# rapidshark-main-breakout-top-mk-1_5.net
KiCad netlist of a schematic drawn in EAGLE
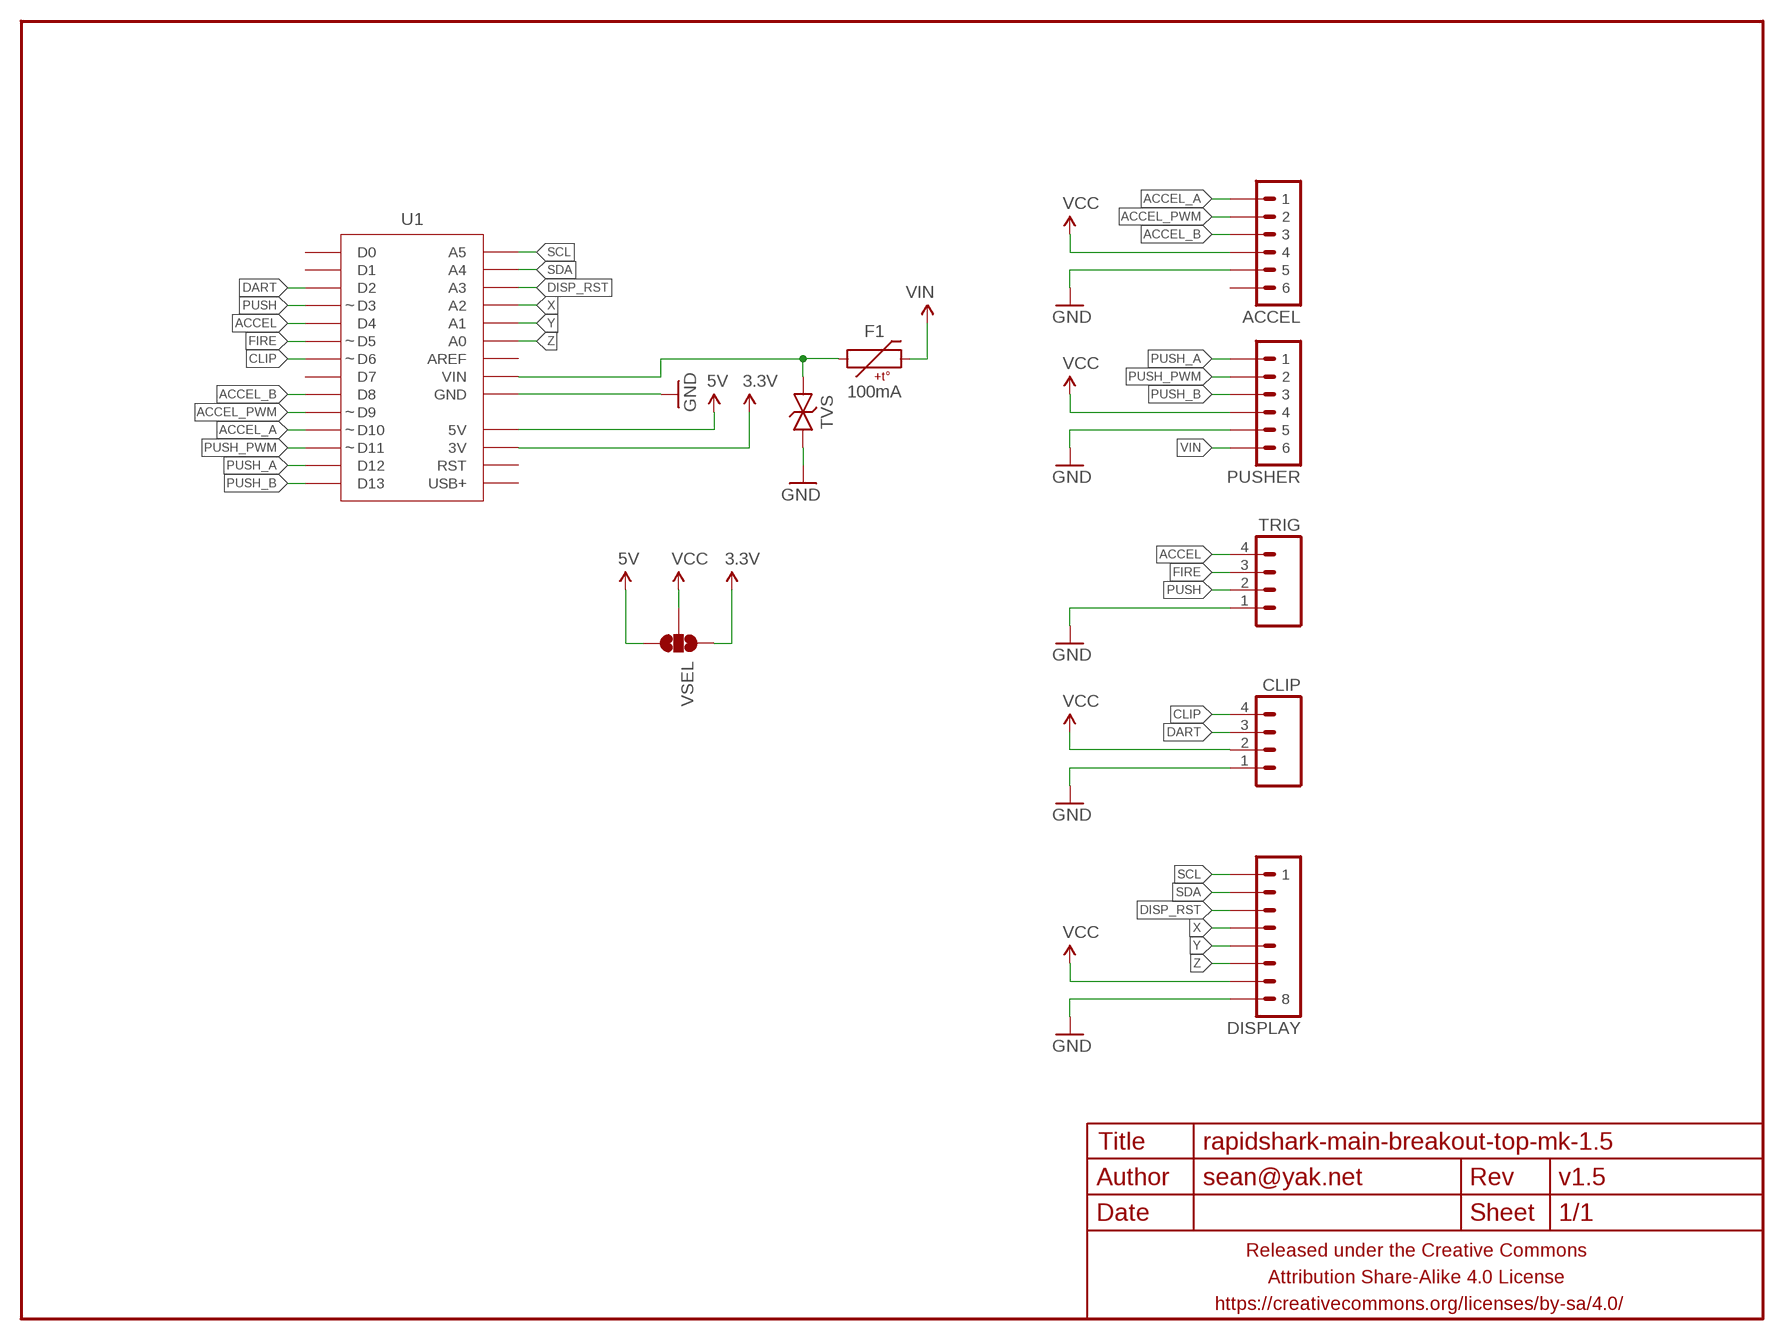
[diagram p0: schematic, sheet 1]

(export (version "E")
  (design (tool "Eeschema 10.0.6"))
  (components
    (comp (ref "ACCEL")
      (value "M06JST-PH-PTH-VERT")
      (footprint "eagle-import:JST-6-PH-VERT-PTH")
      (libsource (lib "eagle-import") (part "M06JST-PH-PTH-VERT"))
    )
    (comp (ref "CLIP")
      (value "M04JST-PTH-VERT")
      (footprint "eagle-import:JST-4-PH-VERT-PTH")
      (libsource (lib "eagle-import") (part "M04JST-PTH-VERT"))
    )
    (comp (ref "DISPLAY")
      (value "M08JST-PH-VERT-PTH")
      (footprint "eagle-import:JST-8-VERT-PTH")
      (libsource (lib "eagle-import") (part "M08JST-PH-VERT-PTH"))
    )
    (comp (ref "F1")
      (value "100mA")
      (footprint "eagle-import:PTC-1206")
      (libsource (lib "eagle-import") (part "PTCSMD"))
    )
    (comp (ref "FRAME1")
      (value "FRAME-LETTERNO_PACKAGE")
      (footprint "eagle-import:DUMMY")
      (fields (field (name "DESIGNER") "sean@yak.net") (field (name "VERSION") "v1.5"))
      (libsource (lib "eagle-import") (part "FRAME-LETTERNO_PACKAGE"))
    )
    (comp (ref "PUSHER")
      (value "M06JST-PH-PTH-VERT")
      (footprint "eagle-import:JST-6-PH-VERT-PTH")
      (libsource (lib "eagle-import") (part "M06JST-PH-PTH-VERT"))
    )
    (comp (ref "TRIG")
      (value "M04JST-PTH-VERT")
      (footprint "eagle-import:JST-4-PH-VERT-PTH")
      (libsource (lib "eagle-import") (part "M04JST-PTH-VERT"))
    )
    (comp (ref "TVS")
      (value "TVSSMA")
      (footprint "eagle-import:SMA-DIODE-TVS-BIDIR")
      (libsource (lib "eagle-import") (part "TVSSMA"))
    )
    (comp (ref "U1")
      (value "ADAFRUIT_METRO_MININOSILK-AMBI2")
      (footprint "eagle-import:ADAFRUIT_METRO_MINI_BACK")
      (libsource (lib "eagle-import") (part "ADAFRUIT_METRO_MININOSILK-AMBI2"))
    )
    (comp (ref "VSEL")
      (value "JUMPER-PAD-3-NOFULL_BOX_SILK")
      (footprint "eagle-import:PAD-JUMPER-3-NO_YES_SILK_FULL_BOX")
      (libsource (lib "eagle-import") (part "JUMPER-PAD-3-NOFULL_BOX_SILK"))
    )
  )
  (nets
    (net (code "1") (name "3.3V") (class "Default")
      (node (ref "U1") (pin "17") (pinfunction "3V_17") (pintype "bidirectional"))
      (node (ref "VSEL") (pin "1") (pinfunction "1_1") (pintype "passive"))
    )
    (net (code "2") (name "5V") (class "Default")
      (node (ref "U1") (pin "18") (pinfunction "5V_18") (pintype "bidirectional"))
      (node (ref "VSEL") (pin "3") (pinfunction "3_3") (pintype "passive"))
    )
    (net (code "3") (name "ACCEL") (class "Default")
      (node (ref "TRIG") (pin "4") (pinfunction "4_4") (pintype "passive"))
      (node (ref "U1") (pin "5") (pinfunction "D4_5") (pintype "bidirectional"))
    )
    (net (code "4") (name "ACCEL_A") (class "Default")
      (node (ref "ACCEL") (pin "1") (pinfunction "1_1") (pintype "passive"))
      (node (ref "U1") (pin "11") (pinfunction "D10_11") (pintype "bidirectional"))
    )
    (net (code "5") (name "ACCEL_B") (class "Default")
      (node (ref "ACCEL") (pin "3") (pinfunction "3_3") (pintype "passive"))
      (node (ref "U1") (pin "9") (pinfunction "D8_9") (pintype "bidirectional"))
    )
    (net (code "6") (name "ACCEL_PWM") (class "Default")
      (node (ref "ACCEL") (pin "2") (pinfunction "2_2") (pintype "passive"))
      (node (ref "U1") (pin "10") (pinfunction "D9_10") (pintype "bidirectional"))
    )
    (net (code "7") (name "CLIP") (class "Default")
      (node (ref "CLIP") (pin "4") (pinfunction "4_4") (pintype "passive"))
      (node (ref "U1") (pin "7") (pinfunction "D6_7") (pintype "bidirectional"))
    )
    (net (code "8") (name "DART") (class "Default")
      (node (ref "CLIP") (pin "3") (pinfunction "3_3") (pintype "passive"))
      (node (ref "U1") (pin "3") (pinfunction "D2_3") (pintype "bidirectional"))
    )
    (net (code "9") (name "DISP_RST") (class "Default")
      (node (ref "DISPLAY") (pin "3") (pinfunction "3_3") (pintype "passive"))
      (node (ref "U1") (pin "26") (pinfunction "A3_26") (pintype "bidirectional"))
    )
    (net (code "10") (name "FIRE") (class "Default")
      (node (ref "TRIG") (pin "3") (pinfunction "3_3") (pintype "passive"))
      (node (ref "U1") (pin "6") (pinfunction "D5_6") (pintype "bidirectional"))
    )
    (net (code "11") (name "GND") (class "Default")
      (node (ref "ACCEL") (pin "5") (pinfunction "5_5") (pintype "passive"))
      (node (ref "CLIP") (pin "1") (pinfunction "1_1") (pintype "passive"))
      (node (ref "DISPLAY") (pin "8") (pinfunction "8_8") (pintype "passive"))
      (node (ref "PUSHER") (pin "5") (pinfunction "5_5") (pintype "passive"))
      (node (ref "TRIG") (pin "1") (pinfunction "1_1") (pintype "passive"))
      (node (ref "TVS") (pin "1") (pinfunction "1_1") (pintype "passive"))
      (node (ref "U1") (pin "19") (pinfunction "GND_19") (pintype "bidirectional"))
      (node (ref "U1") (pin "20") (pinfunction "GND_20") (pintype "bidirectional"))
    )
    (net (code "12") (name "Net-(U1-VIN)") (class "Default")
      (node (ref "F1") (pin "1") (pinfunction "1_1") (pintype "passive"))
      (node (ref "TVS") (pin "2") (pinfunction "2_2") (pintype "passive"))
      (node (ref "U1") (pin "21") (pinfunction "VIN_21") (pintype "bidirectional"))
    )
    (net (code "13") (name "PUSH") (class "Default")
      (node (ref "TRIG") (pin "2") (pinfunction "2_2") (pintype "passive"))
      (node (ref "U1") (pin "4") (pinfunction "D3_4") (pintype "bidirectional"))
    )
    (net (code "14") (name "PUSH_A") (class "Default")
      (node (ref "PUSHER") (pin "1") (pinfunction "1_1") (pintype "passive"))
      (node (ref "U1") (pin "13") (pinfunction "D12_13") (pintype "bidirectional"))
    )
    (net (code "15") (name "PUSH_B") (class "Default")
      (node (ref "PUSHER") (pin "3") (pinfunction "3_3") (pintype "passive"))
      (node (ref "U1") (pin "14") (pinfunction "D13_14") (pintype "bidirectional"))
    )
    (net (code "16") (name "PUSH_PWM") (class "Default")
      (node (ref "PUSHER") (pin "2") (pinfunction "2_2") (pintype "passive"))
      (node (ref "U1") (pin "12") (pinfunction "D11_12") (pintype "bidirectional"))
    )
    (net (code "17") (name "SCL") (class "Default")
      (node (ref "DISPLAY") (pin "1") (pinfunction "1_1") (pintype "passive"))
      (node (ref "U1") (pin "28") (pinfunction "A5_28") (pintype "bidirectional"))
    )
    (net (code "18") (name "SDA") (class "Default")
      (node (ref "DISPLAY") (pin "2") (pinfunction "2_2") (pintype "passive"))
      (node (ref "U1") (pin "27") (pinfunction "A4_27") (pintype "bidirectional"))
    )
    (net (code "19") (name "VCC") (class "Default")
      (node (ref "ACCEL") (pin "4") (pinfunction "4_4") (pintype "passive"))
      (node (ref "CLIP") (pin "2") (pinfunction "2_2") (pintype "passive"))
      (node (ref "DISPLAY") (pin "7") (pinfunction "7_7") (pintype "passive"))
      (node (ref "PUSHER") (pin "4") (pinfunction "4_4") (pintype "passive"))
      (node (ref "VSEL") (pin "2") (pinfunction "2_2") (pintype "passive"))
    )
    (net (code "20") (name "VIN") (class "Default")
      (node (ref "F1") (pin "2") (pinfunction "2_2") (pintype "passive"))
      (node (ref "PUSHER") (pin "6") (pinfunction "6_6") (pintype "passive"))
    )
    (net (code "21") (name "X") (class "Default")
      (node (ref "DISPLAY") (pin "4") (pinfunction "4_4") (pintype "passive"))
      (node (ref "U1") (pin "25") (pinfunction "A2_25") (pintype "bidirectional"))
    )
    (net (code "22") (name "Y") (class "Default")
      (node (ref "DISPLAY") (pin "5") (pinfunction "5_5") (pintype "passive"))
      (node (ref "U1") (pin "24") (pinfunction "A1_24") (pintype "bidirectional"))
    )
    (net (code "23") (name "Z") (class "Default")
      (node (ref "DISPLAY") (pin "6") (pinfunction "6_6") (pintype "passive"))
      (node (ref "U1") (pin "23") (pinfunction "A0_23") (pintype "bidirectional"))
    )
    (net (code "24") (name "unconnected-(ACCEL-Pad6)") (class "Default")
      (node (ref "ACCEL") (pin "6") (pinfunction "6_6") (pintype "passive"))
    )
    (net (code "25") (name "unconnected-(U1-AREF-Pad22)") (class "Default")
      (node (ref "U1") (pin "22") (pinfunction "AREF_22") (pintype "bidirectional"))
    )
    (net (code "26") (name "unconnected-(U1-D0-Pad1)") (class "Default")
      (node (ref "U1") (pin "1") (pinfunction "D0_1") (pintype "bidirectional"))
    )
    (net (code "27") (name "unconnected-(U1-D1-Pad2)") (class "Default")
      (node (ref "U1") (pin "2") (pinfunction "D1_2") (pintype "bidirectional"))
    )
    (net (code "28") (name "unconnected-(U1-D7-Pad8)") (class "Default")
      (node (ref "U1") (pin "8") (pinfunction "D7_8") (pintype "bidirectional"))
    )
    (net (code "29") (name "unconnected-(U1-RST-Pad16)") (class "Default")
      (node (ref "U1") (pin "16") (pinfunction "RST_16") (pintype "bidirectional"))
    )
    (net (code "30") (name "unconnected-(U1-USB+-Pad15)") (class "Default")
      (node (ref "U1") (pin "15") (pinfunction "USB+_15") (pintype "bidirectional"))
    )
  )
)
